# SCH4_Main_Computer_USB.net
KiCad netlist of a schematic drawn in Altium Designer
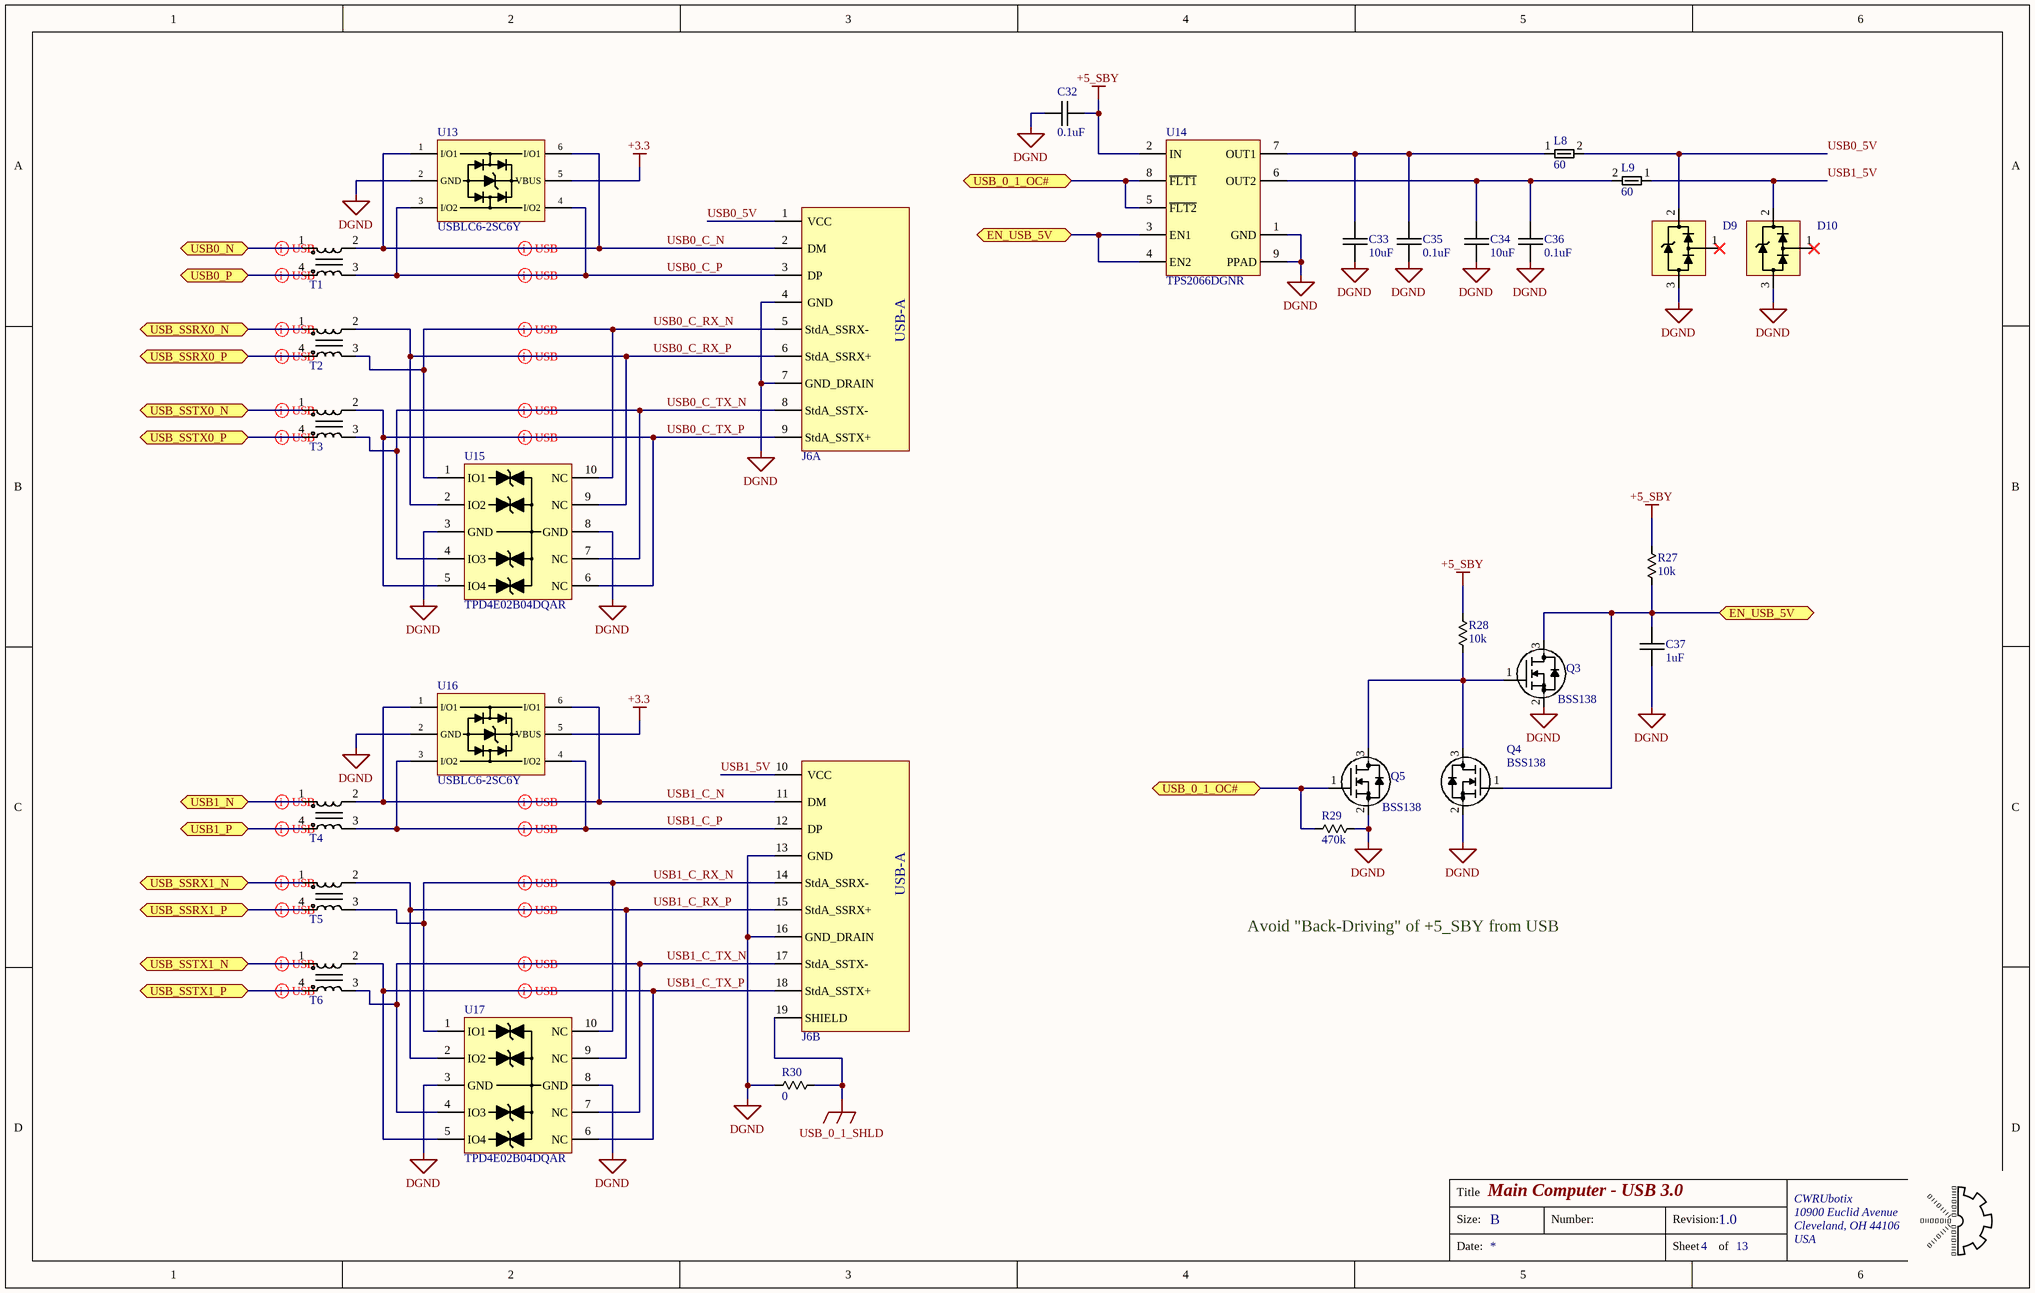
[diagram p0: SCH4_Main_Computer_USB.SchDoc]

(export (version "E")
  (design (tool "Eeschema 10.0.6"))
  (components
    (comp (ref "C32")
      (value "0.1uF")
      (footprint "chip_0603")
      (description "CAP, 0.1uF, ±10%, 16V, X7R, 0603")
      (fields (field (name "PART NUMBER") "CAP-00542") (field (name "TOLERANCE") "±10%"))
      (libsource (lib "Capacitors$") (part "CAP-00542"))
    )
    (comp (ref "C33")
      (value "10uF")
      (footprint "chip_1206")
      (description "CAP, 10uF, ±10%, 25V, X7R, 1206")
      (fields (field (name "PART NUMBER") "CAP-00539") (field (name "TOLERANCE") "±10%"))
      (libsource (lib "Capacitors$") (part "CAP-00539"))
    )
    (comp (ref "C34")
      (value "10uF")
      (footprint "chip_1206")
      (description "CAP, 10uF, ±10%, 25V, X7R, 1206")
      (fields (field (name "PART NUMBER") "CAP-00539") (field (name "TOLERANCE") "±10%"))
      (libsource (lib "Capacitors$") (part "CAP-00539"))
    )
    (comp (ref "C35")
      (value "0.1uF")
      (footprint "chip_0603")
      (description "CAP, 0.1uF, ±10%, 16V, X7R, 0603")
      (fields (field (name "PART NUMBER") "CAP-00542") (field (name "TOLERANCE") "±10%"))
      (libsource (lib "Capacitors$") (part "CAP-00542"))
    )
    (comp (ref "C36")
      (value "0.1uF")
      (footprint "chip_0603")
      (description "CAP, 0.1uF, ±10%, 16V, X7R, 0603")
      (fields (field (name "PART NUMBER") "CAP-00542") (field (name "TOLERANCE") "±10%"))
      (libsource (lib "Capacitors$") (part "CAP-00542"))
    )
    (comp (ref "C37")
      (value "1uF")
      (footprint "chip_0805")
      (description "CAP, 1uF, 10%, 16V, X7R, 0805")
      (fields (field (name "PART NUMBER") "CAP-00110") (field (name "TOLERANCE") "10%"))
      (libsource (lib "Capacitors$") (part "CAP-00110"))
    )
    (comp (ref "D9")
      (value "DLPT05")
      (footprint "sot-23-3")
      (description "TVS, Steering (Rail-Rail), 9.8V Clamping, 17A Peak Pulse, SOT-23")
      (fields (field (name "PART NUMBER") "DIO-00057") (field (name "MANUFACTURER") "Diodes Incorporated"))
      (libsource (lib "Diodes$") (part "DIO-00057"))
    )
    (comp (ref "D10")
      (value "DLPT05")
      (footprint "sot-23-3")
      (description "TVS, Steering (Rail-Rail), 9.8V Clamping, 17A Peak Pulse, SOT-23")
      (fields (field (name "PART NUMBER") "DIO-00057") (field (name "MANUFACTURER") "Diodes Incorporated"))
      (libsource (lib "Diodes$") (part "DIO-00057"))
    )
    (comp (ref "J6")
      (value "1003-004-01010")
      (footprint "CNC_TECH_1003-004-01010")
      (description "USB-A Jack x2, USB 3.0, Right-Angle, Thru-Hole")
      (fields (field (name "PART NUMBER") "CONN-00079") (field (name "MANUFACTURER") "CNC Tech"))
      (libsource (lib "Connectors$") (part "CONN-00079"))
    )
    (comp (ref "L8")
      (value "bead_0")
      (footprint "CHIP_0805_FE")
      (description "Fe Bead, 60 @ 100MH, 3A, 0805")
      (fields
        (field (name "PART NUMBER") "MAG-00125")
        (field (name "IMPEDANCE") "60")
        (field (name "MANUFACTURER") "Pulse Electronics")
      )
      (libsource (lib "Magnetics$") (part "MAG-00125"))
    )
    (comp (ref "L9")
      (value "bead_0")
      (footprint "CHIP_0805_FE")
      (description "Fe Bead, 60 @ 100MH, 3A, 0805")
      (fields
        (field (name "PART NUMBER") "MAG-00125")
        (field (name "IMPEDANCE") "60")
        (field (name "MANUFACTURER") "Pulse Electronics")
      )
      (libsource (lib "Magnetics$") (part "MAG-00125"))
    )
    (comp (ref "Q3")
      (value "n-mosfet_1")
      (footprint "sot-23-3")
      (description "XSTR NMOS, 220mA, 50V, Vgs 1.3V, SOT-23-3")
      (fields
        (field (name "PART NUMBER") "XSTR-00017")
        (field (name "MANUFACTURER") "ON Semi")
        (field (name "MANUFACTURER PN") "BSS138")
      )
      (libsource (lib "Transistors$") (part "XSTR-00017"))
    )
    (comp (ref "Q4")
      (value "n-mosfet_1")
      (footprint "sot-23-3")
      (description "XSTR NMOS, 220mA, 50V, Vgs 1.3V, SOT-23-3")
      (fields
        (field (name "PART NUMBER") "XSTR-00017")
        (field (name "MANUFACTURER") "ON Semi")
        (field (name "MANUFACTURER PN") "BSS138")
      )
      (libsource (lib "Transistors$") (part "XSTR-00017"))
    )
    (comp (ref "Q5")
      (value "n-mosfet_1")
      (footprint "sot-23-3")
      (description "XSTR NMOS, 220mA, 50V, Vgs 1.3V, SOT-23-3")
      (fields
        (field (name "PART NUMBER") "XSTR-00017")
        (field (name "MANUFACTURER") "ON Semi")
        (field (name "MANUFACTURER PN") "BSS138")
      )
      (libsource (lib "Transistors$") (part "XSTR-00017"))
    )
    (comp (ref "R27")
      (value "10k")
      (footprint "chip_0603")
      (description "RES SMD 10K OHM 1% 1/4W 0603")
      (fields (field (name "PART NUMBER") "RES-00306") (field (name "TOLERANCE") "1%"))
      (libsource (lib "Resistors$") (part "RES-00306"))
    )
    (comp (ref "R28")
      (value "10k")
      (footprint "chip_0603")
      (description "RES SMD 10K OHM 1% 1/4W 0603")
      (fields (field (name "PART NUMBER") "RES-00306") (field (name "TOLERANCE") "1%"))
      (libsource (lib "Resistors$") (part "RES-00306"))
    )
    (comp (ref "R29")
      (value "470k")
      (footprint "chip_0603")
      (description "RES SMD 470K OHM 1% 1/4W 0603")
      (fields (field (name "PART NUMBER") "RES-00489") (field (name "TOLERANCE") "1%"))
      (libsource (lib "Resistors$") (part "RES-00489"))
    )
    (comp (ref "R30")
      (value "0")
      (footprint "chip_0805")
      (description "RES SMD 0 OHM 1/8W 0805 Thick Film")
      (fields (field (name "PART NUMBER") "RES-00720") (field (name "TOLERANCE") "Jumper"))
      (libsource (lib "Resistors$") (part "RES-00720"))
    )
    (comp (ref "T1")
      (value "DLW21HN900SQ2L")
      (footprint "MURATA_DLW21H")
      (description "CMC, 330mA 2-CH 90 OHM @ 100MHz SMD")
      (fields (field (name "PART NUMBER") "MAG-00121") (field (name "MANUFACTURER") "Murata"))
      (libsource (lib "Magnetics$") (part "MAG-00121"))
    )
    (comp (ref "T2")
      (value "DLW21HN900SQ2L")
      (footprint "MURATA_DLW21H")
      (description "CMC, 330mA 2-CH 90 OHM @ 100MHz SMD")
      (fields (field (name "PART NUMBER") "MAG-00121") (field (name "MANUFACTURER") "Murata"))
      (libsource (lib "Magnetics$") (part "MAG-00121"))
    )
    (comp (ref "T3")
      (value "DLW21HN900SQ2L")
      (footprint "MURATA_DLW21H")
      (description "CMC, 330mA 2-CH 90 OHM @ 100MHz SMD")
      (fields (field (name "PART NUMBER") "MAG-00121") (field (name "MANUFACTURER") "Murata"))
      (libsource (lib "Magnetics$") (part "MAG-00121"))
    )
    (comp (ref "T4")
      (value "DLW21HN900SQ2L")
      (footprint "MURATA_DLW21H")
      (description "CMC, 330mA 2-CH 90 OHM @ 100MHz SMD")
      (fields (field (name "PART NUMBER") "MAG-00121") (field (name "MANUFACTURER") "Murata"))
      (libsource (lib "Magnetics$") (part "MAG-00121"))
    )
    (comp (ref "T5")
      (value "DLW21HN900SQ2L")
      (footprint "MURATA_DLW21H")
      (description "CMC, 330mA 2-CH 90 OHM @ 100MHz SMD")
      (fields (field (name "PART NUMBER") "MAG-00121") (field (name "MANUFACTURER") "Murata"))
      (libsource (lib "Magnetics$") (part "MAG-00121"))
    )
    (comp (ref "T6")
      (value "DLW21HN900SQ2L")
      (footprint "MURATA_DLW21H")
      (description "CMC, 330mA 2-CH 90 OHM @ 100MHz SMD")
      (fields (field (name "PART NUMBER") "MAG-00121") (field (name "MANUFACTURER") "Murata"))
      (libsource (lib "Magnetics$") (part "MAG-00121"))
    )
    (comp (ref "U13")
      (value "USBLC6-2SC6Y")
      (footprint "sot-23-6")
      (description "ESD Protec, 2-Ch, 2.5pF, 17V clamping voltage, SOT23-6")
      (fields (field (name "PART NUMBER") "DIO-00069") (field (name "MANUFACTURER") "ST"))
      (libsource (lib "Diodes$") (part "DIO-00069"))
    )
    (comp (ref "U14")
      (value "TPS2066DGNR")
      (footprint "VSSOP-8-PPAD")
      (description "IC, Power Switch 1:2, 8-MSOP")
      (fields (field (name "PART NUMBER") "PWREG-00052") (field (name "MANUFACTURER") "TI"))
      (libsource (lib "Power Reg$") (part "PWREG-00052"))
    )
    (comp (ref "U15")
      (value "TPD4E02B04DQAR")
      (footprint "USON-10")
      (description "TVS, 4-Ch, ESD Protec, 3.6V 8.8V 10-USON")
      (fields (field (name "PART NUMBER") "DIO-00068") (field (name "MANUFACTURER") "TI"))
      (libsource (lib "Diodes$") (part "DIO-00068"))
    )
    (comp (ref "U16")
      (value "USBLC6-2SC6Y")
      (footprint "sot-23-6")
      (description "ESD Protec, 2-Ch, 2.5pF, 17V clamping voltage, SOT23-6")
      (fields (field (name "PART NUMBER") "DIO-00069") (field (name "MANUFACTURER") "ST"))
      (libsource (lib "Diodes$") (part "DIO-00069"))
    )
    (comp (ref "U17")
      (value "TPD4E02B04DQAR")
      (footprint "USON-10")
      (description "TVS, 4-Ch, ESD Protec, 3.6V 8.8V 10-USON")
      (fields (field (name "PART NUMBER") "DIO-00068") (field (name "MANUFACTURER") "TI"))
      (libsource (lib "Diodes$") (part "DIO-00068"))
    )
  )
  (nets
    (net (code "1") (name "+3.3") (class "Default")
      (node (ref "U13") (pin "5") (pinfunction "VBUS_5") (pintype "passive"))
      (node (ref "U16") (pin "5") (pinfunction "VBUS_5") (pintype "passive"))
    )
    (net (code "2") (name "+5_SBY") (class "Default")
      (node (ref "C32") (pin "2") (pinfunction "2_2") (pintype "passive"))
      (node (ref "R27") (pin "1") (pinfunction "1_1") (pintype "passive"))
      (node (ref "R28") (pin "1") (pinfunction "1_1") (pintype "passive"))
      (node (ref "U14") (pin "2") (pinfunction "IN_2") (pintype "passive"))
    )
    (net (code "3") (name "/EN_USB_5V") (class "Default")
      (node (ref "C37") (pin "1") (pinfunction "1_1") (pintype "passive"))
      (node (ref "Q3") (pin "3") (pinfunction "D_3") (pintype "passive"))
      (node (ref "Q4") (pin "1") (pinfunction "G_1") (pintype "passive"))
      (node (ref "R27") (pin "2") (pinfunction "2_2") (pintype "passive"))
      (node (ref "U14") (pin "3") (pinfunction "EN1_3") (pintype "passive"))
      (node (ref "U14") (pin "4") (pinfunction "EN2_4") (pintype "passive"))
    )
    (net (code "4") (name "/USB0_5V") (class "Default")
      (node (ref "D9") (pin "2") (pinfunction "VCC_2") (pintype "passive"))
      (node (ref "J6") (pin "1") (pinfunction "VCC_1") (pintype "passive"))
      (node (ref "L8") (pin "2") (pinfunction "2_2") (pintype "passive"))
    )
    (net (code "5") (name "/USB0_C_N") (class "Default")
      (node (ref "J6") (pin "2") (pinfunction "DM_2") (pintype "passive"))
      (node (ref "T1") (pin "2") (pinfunction "2_2") (pintype "passive"))
      (node (ref "U13") (pin "1") (pinfunction "I/O1_1") (pintype "passive"))
      (node (ref "U13") (pin "6") (pinfunction "I/O1_6") (pintype "passive"))
    )
    (net (code "6") (name "/USB0_C_P") (class "Default")
      (node (ref "J6") (pin "3") (pinfunction "DP_3") (pintype "passive"))
      (node (ref "T1") (pin "3") (pinfunction "3_3") (pintype "passive"))
      (node (ref "U13") (pin "3") (pinfunction "I/O2_3") (pintype "passive"))
      (node (ref "U13") (pin "4") (pinfunction "I/O2_4") (pintype "passive"))
    )
    (net (code "7") (name "/USB0_C_RX_N") (class "Default")
      (node (ref "J6") (pin "5") (pinfunction "StdA_SSRX-_5") (pintype "passive"))
      (node (ref "T2") (pin "3") (pinfunction "3_3") (pintype "passive"))
      (node (ref "U15") (pin "1") (pinfunction "IO1_1") (pintype "passive"))
      (node (ref "U15") (pin "10") (pinfunction "NC_10") (pintype "passive"))
    )
    (net (code "8") (name "/USB0_C_RX_P") (class "Default")
      (node (ref "J6") (pin "6") (pinfunction "StdA_SSRX+_6") (pintype "passive"))
      (node (ref "T2") (pin "2") (pinfunction "2_2") (pintype "passive"))
      (node (ref "U15") (pin "2") (pinfunction "IO2_2") (pintype "passive"))
      (node (ref "U15") (pin "9") (pinfunction "NC_9") (pintype "passive"))
    )
    (net (code "9") (name "/USB0_C_TX_N") (class "Default")
      (node (ref "J6") (pin "8") (pinfunction "StdA_SSTX-_8") (pintype "passive"))
      (node (ref "T3") (pin "3") (pinfunction "3_3") (pintype "passive"))
      (node (ref "U15") (pin "4") (pinfunction "IO3_4") (pintype "passive"))
      (node (ref "U15") (pin "7") (pinfunction "NC_7") (pintype "passive"))
    )
    (net (code "10") (name "/USB0_C_TX_P") (class "Default")
      (node (ref "J6") (pin "9") (pinfunction "StdA_SSTX+_9") (pintype "passive"))
      (node (ref "T3") (pin "2") (pinfunction "2_2") (pintype "passive"))
      (node (ref "U15") (pin "5") (pinfunction "IO4_5") (pintype "passive"))
      (node (ref "U15") (pin "6") (pinfunction "NC_6") (pintype "passive"))
    )
    (net (code "11") (name "/USB0_N") (class "Default")
      (node (ref "T1") (pin "1") (pinfunction "1_1") (pintype "passive"))
    )
    (net (code "12") (name "/USB0_P") (class "Default")
      (node (ref "T1") (pin "4") (pinfunction "34_4") (pintype "passive"))
    )
    (net (code "13") (name "/USB1_5V") (class "Default")
      (node (ref "D10") (pin "2") (pinfunction "VCC_2") (pintype "passive"))
      (node (ref "J6") (pin "10") (pinfunction "VCC_10") (pintype "passive"))
      (node (ref "L9") (pin "1") (pinfunction "1_1") (pintype "passive"))
    )
    (net (code "14") (name "/USB1_C_N") (class "Default")
      (node (ref "J6") (pin "11") (pinfunction "DM_11") (pintype "passive"))
      (node (ref "T4") (pin "2") (pinfunction "2_2") (pintype "passive"))
      (node (ref "U16") (pin "1") (pinfunction "I/O1_1") (pintype "passive"))
      (node (ref "U16") (pin "6") (pinfunction "I/O1_6") (pintype "passive"))
    )
    (net (code "15") (name "/USB1_C_P") (class "Default")
      (node (ref "J6") (pin "12") (pinfunction "DP_12") (pintype "passive"))
      (node (ref "T4") (pin "3") (pinfunction "3_3") (pintype "passive"))
      (node (ref "U16") (pin "3") (pinfunction "I/O2_3") (pintype "passive"))
      (node (ref "U16") (pin "4") (pinfunction "I/O2_4") (pintype "passive"))
    )
    (net (code "16") (name "/USB1_C_RX_N") (class "Default")
      (node (ref "J6") (pin "14") (pinfunction "StdA_SSRX-_14") (pintype "passive"))
      (node (ref "T5") (pin "3") (pinfunction "3_3") (pintype "passive"))
      (node (ref "U17") (pin "1") (pinfunction "IO1_1") (pintype "passive"))
      (node (ref "U17") (pin "10") (pinfunction "NC_10") (pintype "passive"))
    )
    (net (code "17") (name "/USB1_C_RX_P") (class "Default")
      (node (ref "J6") (pin "15") (pinfunction "StdA_SSRX+_15") (pintype "passive"))
      (node (ref "T5") (pin "2") (pinfunction "2_2") (pintype "passive"))
      (node (ref "U17") (pin "2") (pinfunction "IO2_2") (pintype "passive"))
      (node (ref "U17") (pin "9") (pinfunction "NC_9") (pintype "passive"))
    )
    (net (code "18") (name "/USB1_C_TX_N") (class "Default")
      (node (ref "J6") (pin "17") (pinfunction "StdA_SSTX-_17") (pintype "passive"))
      (node (ref "T6") (pin "3") (pinfunction "3_3") (pintype "passive"))
      (node (ref "U17") (pin "4") (pinfunction "IO3_4") (pintype "passive"))
      (node (ref "U17") (pin "7") (pinfunction "NC_7") (pintype "passive"))
    )
    (net (code "19") (name "/USB1_C_TX_P") (class "Default")
      (node (ref "J6") (pin "18") (pinfunction "StdA_SSTX+_18") (pintype "passive"))
      (node (ref "T6") (pin "2") (pinfunction "2_2") (pintype "passive"))
      (node (ref "U17") (pin "5") (pinfunction "IO4_5") (pintype "passive"))
      (node (ref "U17") (pin "6") (pinfunction "NC_6") (pintype "passive"))
    )
    (net (code "20") (name "/USB1_N") (class "Default")
      (node (ref "T4") (pin "1") (pinfunction "1_1") (pintype "passive"))
    )
    (net (code "21") (name "/USB1_P") (class "Default")
      (node (ref "T4") (pin "4") (pinfunction "34_4") (pintype "passive"))
    )
    (net (code "22") (name "/USB_0_1_OC#") (class "Default")
      (node (ref "Q5") (pin "1") (pinfunction "G_1") (pintype "passive"))
      (node (ref "R29") (pin "1") (pinfunction "1_1") (pintype "passive"))
      (node (ref "U14") (pin "5") (pinfunction "~{FLT2}_5") (pintype "passive"))
      (node (ref "U14") (pin "8") (pinfunction "~{FLT1}_8") (pintype "passive"))
    )
    (net (code "23") (name "/USB_SSRX0_N") (class "Default")
      (node (ref "T2") (pin "1") (pinfunction "1_1") (pintype "passive"))
    )
    (net (code "24") (name "/USB_SSRX0_P") (class "Default")
      (node (ref "T2") (pin "4") (pinfunction "34_4") (pintype "passive"))
    )
    (net (code "25") (name "/USB_SSRX1_N") (class "Default")
      (node (ref "T5") (pin "1") (pinfunction "1_1") (pintype "passive"))
    )
    (net (code "26") (name "/USB_SSRX1_P") (class "Default")
      (node (ref "T5") (pin "4") (pinfunction "34_4") (pintype "passive"))
    )
    (net (code "27") (name "/USB_SSTX0_N") (class "Default")
      (node (ref "T3") (pin "1") (pinfunction "1_1") (pintype "passive"))
    )
    (net (code "28") (name "/USB_SSTX0_P") (class "Default")
      (node (ref "T3") (pin "4") (pinfunction "34_4") (pintype "passive"))
    )
    (net (code "29") (name "/USB_SSTX1_N") (class "Default")
      (node (ref "T6") (pin "1") (pinfunction "1_1") (pintype "passive"))
    )
    (net (code "30") (name "/USB_SSTX1_P") (class "Default")
      (node (ref "T6") (pin "4") (pinfunction "34_4") (pintype "passive"))
    )
    (net (code "31") (name "DGND") (class "Default")
      (node (ref "C32") (pin "1") (pinfunction "1_1") (pintype "passive"))
      (node (ref "C33") (pin "2") (pinfunction "2_2") (pintype "passive"))
      (node (ref "C34") (pin "2") (pinfunction "2_2") (pintype "passive"))
      (node (ref "C35") (pin "1") (pinfunction "1_1") (pintype "passive"))
      (node (ref "C36") (pin "1") (pinfunction "1_1") (pintype "passive"))
      (node (ref "C37") (pin "2") (pinfunction "2_2") (pintype "passive"))
      (node (ref "D10") (pin "3") (pinfunction "GND_3") (pintype "passive"))
      (node (ref "D9") (pin "3") (pinfunction "GND_3") (pintype "passive"))
      (node (ref "J6") (pin "13") (pinfunction "GND_13") (pintype "passive"))
      (node (ref "J6") (pin "16") (pinfunction "GND_DRAIN_16") (pintype "passive"))
      (node (ref "J6") (pin "4") (pinfunction "GND_4") (pintype "passive"))
      (node (ref "J6") (pin "7") (pinfunction "GND_DRAIN_7") (pintype "passive"))
      (node (ref "Q3") (pin "2") (pinfunction "S_2") (pintype "passive"))
      (node (ref "Q4") (pin "2") (pinfunction "S_2") (pintype "passive"))
      (node (ref "Q5") (pin "2") (pinfunction "S_2") (pintype "passive"))
      (node (ref "R29") (pin "2") (pinfunction "2_2") (pintype "passive"))
      (node (ref "R30") (pin "1") (pinfunction "1_1") (pintype "passive"))
      (node (ref "U13") (pin "2") (pinfunction "GND_2") (pintype "passive"))
      (node (ref "U14") (pin "1") (pinfunction "GND_1") (pintype "passive"))
      (node (ref "U14") (pin "9") (pinfunction "PPAD_9") (pintype "passive"))
      (node (ref "U15") (pin "3") (pinfunction "GND_3") (pintype "passive"))
      (node (ref "U15") (pin "8") (pinfunction "GND_8") (pintype "passive"))
      (node (ref "U16") (pin "2") (pinfunction "GND_2") (pintype "passive"))
      (node (ref "U17") (pin "3") (pinfunction "GND_3") (pintype "passive"))
      (node (ref "U17") (pin "8") (pinfunction "GND_8") (pintype "passive"))
    )
    (net (code "32") (name "Net-(Q3-G)") (class "Default")
      (node (ref "Q3") (pin "1") (pinfunction "G_1") (pintype "passive"))
      (node (ref "Q4") (pin "3") (pinfunction "D_3") (pintype "passive"))
      (node (ref "Q5") (pin "3") (pinfunction "D_3") (pintype "passive"))
      (node (ref "R28") (pin "2") (pinfunction "2_2") (pintype "passive"))
    )
    (net (code "33") (name "Net-(U14-OUT1)") (class "Default")
      (node (ref "C33") (pin "1") (pinfunction "1_1") (pintype "passive"))
      (node (ref "C35") (pin "2") (pinfunction "2_2") (pintype "passive"))
      (node (ref "L8") (pin "1") (pinfunction "1_1") (pintype "passive"))
      (node (ref "U14") (pin "7") (pinfunction "OUT1_7") (pintype "passive"))
    )
    (net (code "34") (name "Net-(U14-OUT2)") (class "Default")
      (node (ref "C34") (pin "1") (pinfunction "1_1") (pintype "passive"))
      (node (ref "C36") (pin "2") (pinfunction "2_2") (pintype "passive"))
      (node (ref "L9") (pin "2") (pinfunction "2_2") (pintype "passive"))
      (node (ref "U14") (pin "6") (pinfunction "OUT2_6") (pintype "passive"))
    )
    (net (code "35") (name "USB_0_1_SHLD") (class "Default")
      (node (ref "J6") (pin "19") (pinfunction "SHIELD_19") (pintype "passive"))
      (node (ref "R30") (pin "2") (pinfunction "2_2") (pintype "passive"))
    )
    (net (code "36") (name "unconnected-(D9-LINE-Pad1)") (class "Default")
      (node (ref "D9") (pin "1") (pinfunction "LINE_1") (pintype "passive+no_connect"))
    )
    (net (code "37") (name "unconnected-(D10-LINE-Pad1)") (class "Default")
      (node (ref "D10") (pin "1") (pinfunction "LINE_1") (pintype "passive+no_connect"))
    )
  )
)
